# 01_-_Main.net
KiCad netlist of a schematic drawn in Altium Designer
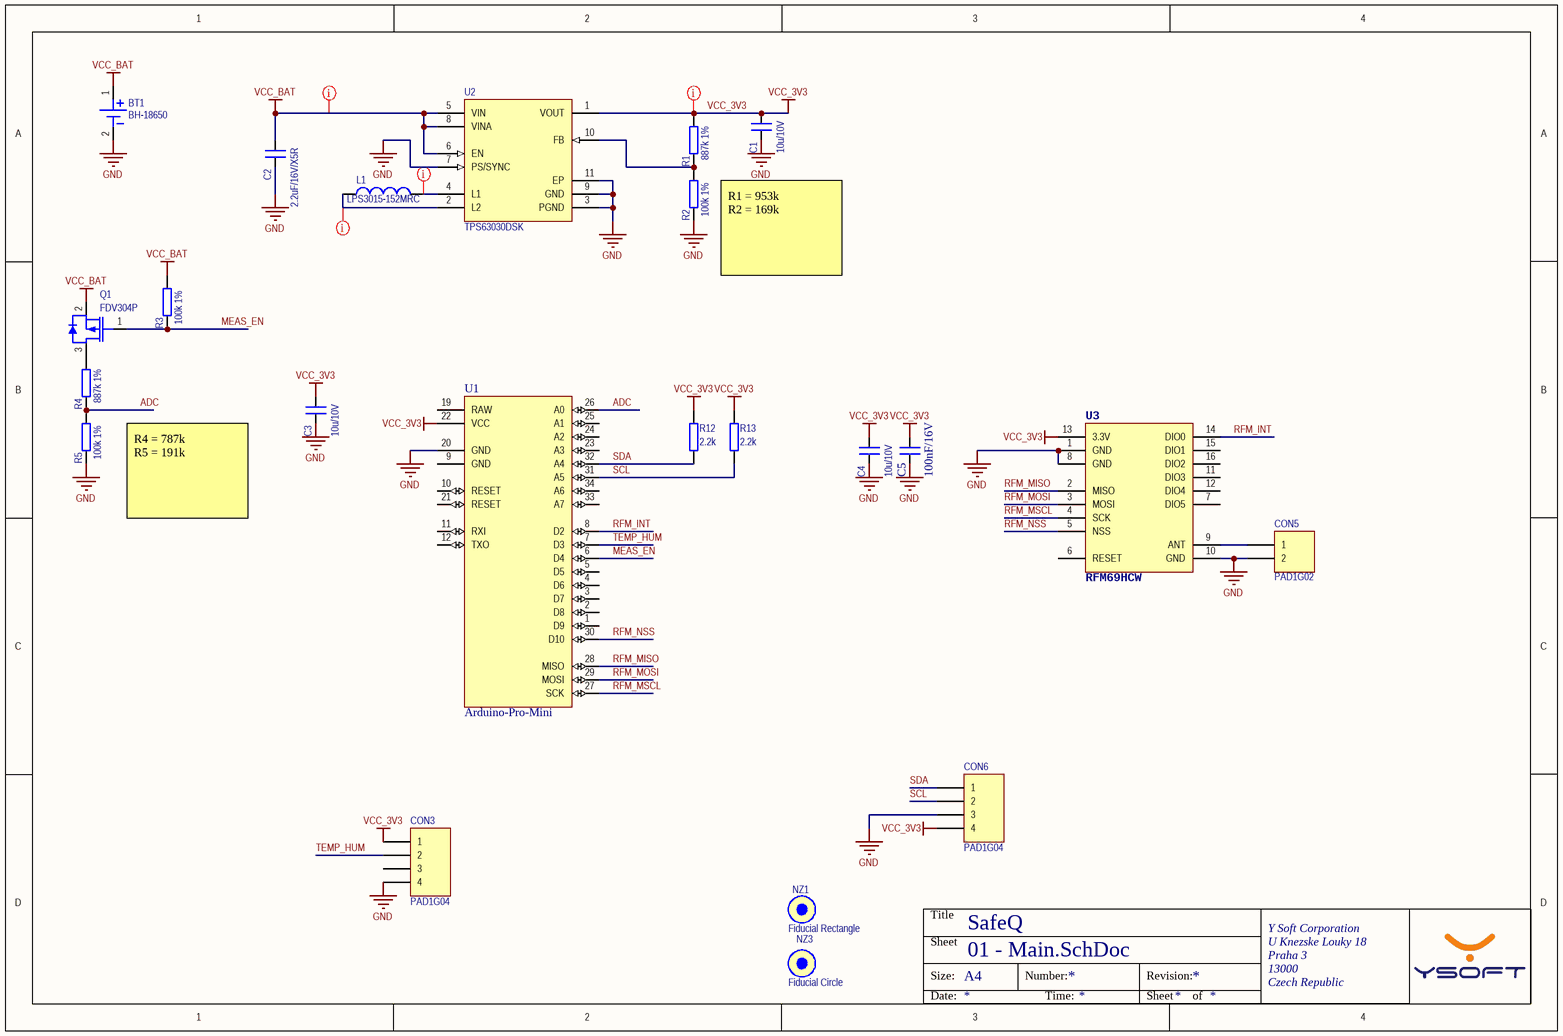
[diagram p0: 01 - Main.SchDoc]

(export (version "E")
  (design (tool "Eeschema 10.0.6"))
  (components
    (comp (ref "BT1") (value "BH-18650") (footprint "BH18650") (libsource (lib "Battery") (part "BH-18650")))
    (comp (ref "C1")
      (value "10u/10V")
      (footprint "C-0805")
      (description "SMD Ceramic Capacitor 0805 10u/10V")
      (libsource (lib "Personal Vault") (part "CapacitorNP"))
    )
    (comp (ref "C2")
      (value "2.2uF/16V/X5R")
      (footprint "C-0603")
      (description "SMD Ceramic Capacitor 0603 2.2uF/16V/X5R")
      (libsource (lib "Personal Vault") (part "CapacitorNP"))
    )
    (comp (ref "C3")
      (value "10u/10V")
      (footprint "C-0805")
      (description "SMD Ceramic Capacitor 0805 10u/10V")
      (libsource (lib "Personal Vault") (part "CapacitorNP"))
    )
    (comp (ref "C4")
      (value "10u/10V")
      (footprint "C-0805")
      (description "SMD Ceramic Capacitor 0805 10u/10V")
      (libsource (lib "Personal Vault") (part "CapacitorNP"))
    )
    (comp (ref "C5")
      (value "100nF/16V")
      (footprint "C-0603")
      (description "SMD Ceramic Capacitor 0603 100nF/16V")
      (libsource (lib "Personal Vault") (part "CapacitorNP"))
    )
    (comp (ref "CON3")
      (value "PAD1G04")
      (footprint "HDR1X04S")
      (description "1x4pin single row pads, 2.54mm")
      (libsource (lib "Personal Vault") (part "Header 4"))
    )
    (comp (ref "CON5")
      (value "PAD1G02")
      (footprint "HDR1X02S")
      (description "1x2pin single row pads, 2.54mm")
      (fields (field (name "PUBLISHER") "Altium Limited"))
      (libsource (lib "Personal Vault") (part "Header 2"))
    )
    (comp (ref "CON6")
      (value "PAD1G04")
      (footprint "HDR1X04S")
      (description "1x4pin single row pads, 2.54mm")
      (libsource (lib "Personal Vault") (part "Header 4"))
    )
    (comp (ref "L1")
      (value "LPS3015-152MRC")
      (footprint "LPS3015")
      (description "Shielded inductor 1.5uH/1.3A 3x3mm")
      (libsource (lib "Personal Vault") (part "Inductor"))
    )
    (comp (ref "NZ1")
      (value "Fiducial Rectangle")
      (footprint "Fiducial Rectangle")
      (libsource (lib "Personal Vault") (part "Fiducial Mark"))
    )
    (comp (ref "NZ3")
      (value "Fiducial Circle")
      (footprint "Fiducial Circle")
      (libsource (lib "Personal Vault") (part "Fiducial Mark"))
    )
    (comp (ref "Q1")
      (value "FDV304P")
      (footprint "SOT23-3L")
      (description "P-Channel Digital FET 25V, 460mA")
      (libsource (lib "Personal Vault") (part "P-MOSFET"))
    )
    (comp (ref "R1")
      (value "887k 1%")
      (footprint "R-0603")
      (description "SMD Resistor 0603 887k 1%")
      (libsource (lib "Personal Vault") (part "Resistor"))
    )
    (comp (ref "R2")
      (value "100k 1%")
      (footprint "R-0603")
      (description "SMD Resistor 0603 100k 1%")
      (libsource (lib "Personal Vault") (part "Resistor"))
    )
    (comp (ref "R3")
      (value "100k 1%")
      (footprint "R-0603")
      (description "SMD Resistor 0603 100k 1%")
      (libsource (lib "Personal Vault") (part "Resistor"))
    )
    (comp (ref "R4")
      (value "887k 1%")
      (footprint "R-0603")
      (description "SMD Resistor 0603 887k 1%")
      (libsource (lib "Personal Vault") (part "Resistor"))
    )
    (comp (ref "R5")
      (value "100k 1%")
      (footprint "R-0603")
      (description "SMD Resistor 0603 100k 1%")
      (libsource (lib "Personal Vault") (part "Resistor"))
    )
    (comp (ref "R12")
      (value "2.2k")
      (footprint "R-0603")
      (description "SMD Resistor 0603 2k2")
      (libsource (lib "Personal Vault") (part "Resistor"))
    )
    (comp (ref "R13")
      (value "2.2k")
      (footprint "R-0603")
      (description "SMD Resistor 0603 2k2")
      (libsource (lib "Personal Vault") (part "Resistor"))
    )
    (comp (ref "U1")
      (value "Arduino-Pro-Mini")
      (footprint "Arduino Mini Pro")
      (libsource (lib "Arduino") (part "Arduino-Pro-Mini"))
    )
    (comp (ref "U2")
      (value "TPS63030DSK")
      (footprint "DSK10-2000X1200TP_V")
      (description "High Efficient Single Inductor Buck-Boost Converter with 1-A Switches")
      (libsource (lib "Personal Vault") (part "TPS63030"))
    )
    (comp (ref "U3")
      (value "RFM69HCW")
      (footprint "RFM:RFM69HCW-XXXS2")
      (libsource (lib "RFM") (part "RFM69HCW"))
    )
  )
  (nets
    (net (code "1") (name "/ADC") (class "Default")
      (node (ref "R4") (pin "1") (pinfunction "1_1") (pintype "passive"))
      (node (ref "R5") (pin "2") (pinfunction "2_2") (pintype "passive"))
      (node (ref "U1") (pin "26") (pinfunction "A0_26") (pintype "bidirectional"))
    )
    (net (code "2") (name "/MEAS_EN") (class "Default")
      (node (ref "Q1") (pin "1") (pinfunction "GATE_1") (pintype "passive"))
      (node (ref "R3") (pin "1") (pinfunction "1_1") (pintype "passive"))
      (node (ref "U1") (pin "6") (pinfunction "D4_6") (pintype "bidirectional"))
    )
    (net (code "3") (name "/RFM_INT") (class "Default")
      (node (ref "U1") (pin "8") (pinfunction "D2_8") (pintype "bidirectional"))
      (node (ref "U3") (pin "14") (pinfunction "DIO0_14") (pintype "passive"))
    )
    (net (code "4") (name "/RFM_MISO") (class "Default")
      (node (ref "U1") (pin "28") (pinfunction "MISO_28") (pintype "bidirectional"))
      (node (ref "U3") (pin "2") (pinfunction "MISO_2") (pintype "passive"))
    )
    (net (code "5") (name "/RFM_MOSI") (class "Default")
      (node (ref "U1") (pin "29") (pinfunction "MOSI_29") (pintype "bidirectional"))
      (node (ref "U3") (pin "3") (pinfunction "MOSI_3") (pintype "passive"))
    )
    (net (code "6") (name "/RFM_MSCL") (class "Default")
      (node (ref "U1") (pin "27") (pinfunction "SCK_27") (pintype "bidirectional"))
      (node (ref "U3") (pin "4") (pinfunction "SCK_4") (pintype "passive"))
    )
    (net (code "7") (name "/RFM_NSS") (class "Default")
      (node (ref "U1") (pin "30") (pinfunction "D10_30") (pintype "bidirectional"))
      (node (ref "U3") (pin "5") (pinfunction "NSS_5") (pintype "passive"))
    )
    (net (code "8") (name "/SCL") (class "Default")
      (node (ref "CON6") (pin "2") (pinfunction "2_2") (pintype "passive"))
      (node (ref "R13") (pin "1") (pinfunction "1_1") (pintype "passive"))
      (node (ref "U1") (pin "31") (pinfunction "A5_31") (pintype "bidirectional"))
    )
    (net (code "9") (name "/SDA") (class "Default")
      (node (ref "CON6") (pin "1") (pinfunction "1_1") (pintype "passive"))
      (node (ref "R12") (pin "1") (pinfunction "1_1") (pintype "passive"))
      (node (ref "U1") (pin "32") (pinfunction "A4_32") (pintype "bidirectional"))
    )
    (net (code "10") (name "/TEMP_HUM") (class "Default")
      (node (ref "CON3") (pin "2") (pinfunction "2_2") (pintype "passive"))
      (node (ref "U1") (pin "7") (pinfunction "D3_7") (pintype "bidirectional"))
    )
    (net (code "11") (name "GND") (class "Default")
      (node (ref "BT1") (pin "2") (pinfunction "-_2") (pintype "passive"))
      (node (ref "C1") (pin "1") (pinfunction "1_1") (pintype "passive"))
      (node (ref "C2") (pin "1") (pinfunction "1_1") (pintype "passive"))
      (node (ref "C3") (pin "1") (pinfunction "1_1") (pintype "passive"))
      (node (ref "C4") (pin "1") (pinfunction "1_1") (pintype "passive"))
      (node (ref "C5") (pin "1") (pinfunction "1_1") (pintype "passive"))
      (node (ref "CON3") (pin "4") (pinfunction "4_4") (pintype "passive"))
      (node (ref "CON5") (pin "2") (pinfunction "2_2") (pintype "passive"))
      (node (ref "CON6") (pin "3") (pinfunction "3_3") (pintype "passive"))
      (node (ref "R2") (pin "1") (pinfunction "1_1") (pintype "passive"))
      (node (ref "R5") (pin "1") (pinfunction "1_1") (pintype "passive"))
      (node (ref "U1") (pin "20") (pinfunction "GND_20") (pintype "power_in"))
      (node (ref "U2") (pin "11") (pinfunction "EP_11") (pintype "power_in"))
      (node (ref "U2") (pin "3") (pinfunction "PGND_3") (pintype "power_in"))
      (node (ref "U2") (pin "7") (pinfunction "PS/SYNC_7") (pintype "input"))
      (node (ref "U2") (pin "9") (pinfunction "GND_9") (pintype "power_in"))
      (node (ref "U3") (pin "1") (pinfunction "GND_1") (pintype "power_in"))
      (node (ref "U3") (pin "10") (pinfunction "GND_10") (pintype "power_in"))
      (node (ref "U3") (pin "8") (pinfunction "GND_8") (pintype "power_in"))
    )
    (net (code "12") (name "Net-(Q1-DRAIN)") (class "Default")
      (node (ref "Q1") (pin "3") (pinfunction "DRAIN_3") (pintype "passive"))
      (node (ref "R4") (pin "2") (pinfunction "2_2") (pintype "passive"))
    )
    (net (code "13") (name "Net-(U2-FB)") (class "Default")
      (node (ref "R1") (pin "1") (pinfunction "1_1") (pintype "passive"))
      (node (ref "R2") (pin "2") (pinfunction "2_2") (pintype "passive"))
      (node (ref "U2") (pin "10") (pinfunction "FB_10") (pintype "input"))
    )
    (net (code "14") (name "Net-(U2-L1)") (class "Default")
      (node (ref "L1") (pin "2") (pinfunction "2_2") (pintype "passive"))
      (node (ref "U2") (pin "4") (pinfunction "L1_4") (pintype "passive"))
    )
    (net (code "15") (name "Net-(U2-L2)") (class "Default")
      (node (ref "L1") (pin "1") (pinfunction "1_1") (pintype "passive"))
      (node (ref "U2") (pin "2") (pinfunction "L2_2") (pintype "passive"))
    )
    (net (code "16") (name "Net-(U3-ANT)") (class "Default")
      (node (ref "CON5") (pin "1") (pinfunction "1_1") (pintype "passive"))
      (node (ref "U3") (pin "9") (pinfunction "ANT_9") (pintype "passive"))
    )
    (net (code "17") (name "VCC_3V3") (class "Default")
      (node (ref "C1") (pin "2") (pinfunction "2_2") (pintype "passive"))
      (node (ref "C3") (pin "2") (pinfunction "2_2") (pintype "passive"))
      (node (ref "C4") (pin "2") (pinfunction "2_2") (pintype "passive"))
      (node (ref "C5") (pin "2") (pinfunction "2_2") (pintype "passive"))
      (node (ref "CON3") (pin "1") (pinfunction "1_1") (pintype "passive"))
      (node (ref "CON6") (pin "4") (pinfunction "4_4") (pintype "passive"))
      (node (ref "R1") (pin "2") (pinfunction "2_2") (pintype "passive"))
      (node (ref "R12") (pin "2") (pinfunction "2_2") (pintype "passive"))
      (node (ref "R13") (pin "2") (pinfunction "2_2") (pintype "passive"))
      (node (ref "U1") (pin "22") (pinfunction "VCC_22") (pintype "power_in"))
      (node (ref "U2") (pin "1") (pinfunction "VOUT_1") (pintype "power_in"))
      (node (ref "U3") (pin "13") (pinfunction "3.3V_13") (pintype "power_in"))
    )
    (net (code "18") (name "VCC_BAT") (class "Default")
      (node (ref "BT1") (pin "1") (pinfunction "+_1") (pintype "passive"))
      (node (ref "C2") (pin "2") (pinfunction "2_2") (pintype "passive"))
      (node (ref "Q1") (pin "2") (pinfunction "SOURCE_2") (pintype "passive"))
      (node (ref "R3") (pin "2") (pinfunction "2_2") (pintype "passive"))
      (node (ref "U2") (pin "5") (pinfunction "VIN_5") (pintype "power_in"))
      (node (ref "U2") (pin "6") (pinfunction "EN_6") (pintype "input"))
      (node (ref "U2") (pin "8") (pinfunction "VINA_8") (pintype "power_in"))
    )
    (net (code "19") (name "unconnected-(CON3-Pad3)") (class "Default")
      (node (ref "CON3") (pin "3") (pinfunction "3_3") (pintype "passive"))
    )
    (net (code "20") (name "unconnected-(U1-A1-Pad25)") (class "Default")
      (node (ref "U1") (pin "25") (pinfunction "A1_25") (pintype "bidirectional"))
    )
    (net (code "21") (name "unconnected-(U1-A2-Pad24)") (class "Default")
      (node (ref "U1") (pin "24") (pinfunction "A2_24") (pintype "bidirectional"))
    )
    (net (code "22") (name "unconnected-(U1-A3-Pad23)") (class "Default")
      (node (ref "U1") (pin "23") (pinfunction "A3_23") (pintype "bidirectional"))
    )
    (net (code "23") (name "unconnected-(U1-A6-Pad34)") (class "Default")
      (node (ref "U1") (pin "34") (pinfunction "A6_34") (pintype "bidirectional"))
    )
    (net (code "24") (name "unconnected-(U1-A7-Pad33)") (class "Default")
      (node (ref "U1") (pin "33") (pinfunction "A7_33") (pintype "bidirectional"))
    )
    (net (code "25") (name "unconnected-(U1-D5-Pad5)") (class "Default")
      (node (ref "U1") (pin "5") (pinfunction "D5_5") (pintype "bidirectional"))
    )
    (net (code "26") (name "unconnected-(U1-D6-Pad4)") (class "Default")
      (node (ref "U1") (pin "4") (pinfunction "D6_4") (pintype "bidirectional"))
    )
    (net (code "27") (name "unconnected-(U1-D7-Pad3)") (class "Default")
      (node (ref "U1") (pin "3") (pinfunction "D7_3") (pintype "bidirectional"))
    )
    (net (code "28") (name "unconnected-(U1-D8-Pad2)") (class "Default")
      (node (ref "U1") (pin "2") (pinfunction "D8_2") (pintype "bidirectional"))
    )
    (net (code "29") (name "unconnected-(U1-D9-Pad1)") (class "Default")
      (node (ref "U1") (pin "1") (pinfunction "D9_1") (pintype "bidirectional"))
    )
    (net (code "30") (name "unconnected-(U1-GND-Pad9)") (class "Default")
      (node (ref "U1") (pin "9") (pinfunction "GND_9") (pintype "power_in"))
    )
    (net (code "31") (name "unconnected-(U1-RAW-Pad19)") (class "Default")
      (node (ref "U1") (pin "19") (pinfunction "RAW_19") (pintype "power_in"))
    )
    (net (code "32") (name "unconnected-(U1-RESET-Pad10)") (class "Default")
      (node (ref "U1") (pin "10") (pinfunction "RESET_10") (pintype "bidirectional"))
    )
    (net (code "33") (name "unconnected-(U1-RESET-Pad21)") (class "Default")
      (node (ref "U1") (pin "21") (pinfunction "RESET_21") (pintype "bidirectional"))
    )
    (net (code "34") (name "unconnected-(U1-RXI-Pad11)") (class "Default")
      (node (ref "U1") (pin "11") (pinfunction "RXI_11") (pintype "bidirectional"))
    )
    (net (code "35") (name "unconnected-(U1-TXO-Pad12)") (class "Default")
      (node (ref "U1") (pin "12") (pinfunction "TXO_12") (pintype "bidirectional"))
    )
    (net (code "36") (name "unconnected-(U3-DIO1-Pad15)") (class "Default")
      (node (ref "U3") (pin "15") (pinfunction "DIO1_15") (pintype "passive"))
    )
    (net (code "37") (name "unconnected-(U3-DIO2-Pad16)") (class "Default")
      (node (ref "U3") (pin "16") (pinfunction "DIO2_16") (pintype "passive"))
    )
    (net (code "38") (name "unconnected-(U3-DIO3-Pad11)") (class "Default")
      (node (ref "U3") (pin "11") (pinfunction "DIO3_11") (pintype "passive"))
    )
    (net (code "39") (name "unconnected-(U3-DIO4-Pad12)") (class "Default")
      (node (ref "U3") (pin "12") (pinfunction "DIO4_12") (pintype "passive"))
    )
    (net (code "40") (name "unconnected-(U3-DIO5-Pad7)") (class "Default")
      (node (ref "U3") (pin "7") (pinfunction "DIO5_7") (pintype "passive"))
    )
    (net (code "41") (name "unconnected-(U3-RESET-Pad6)") (class "Default")
      (node (ref "U3") (pin "6") (pinfunction "RESET_6") (pintype "passive"))
    )
  )
)
